# untitled.net
KiCad netlist of a schematic drawn in EAGLE
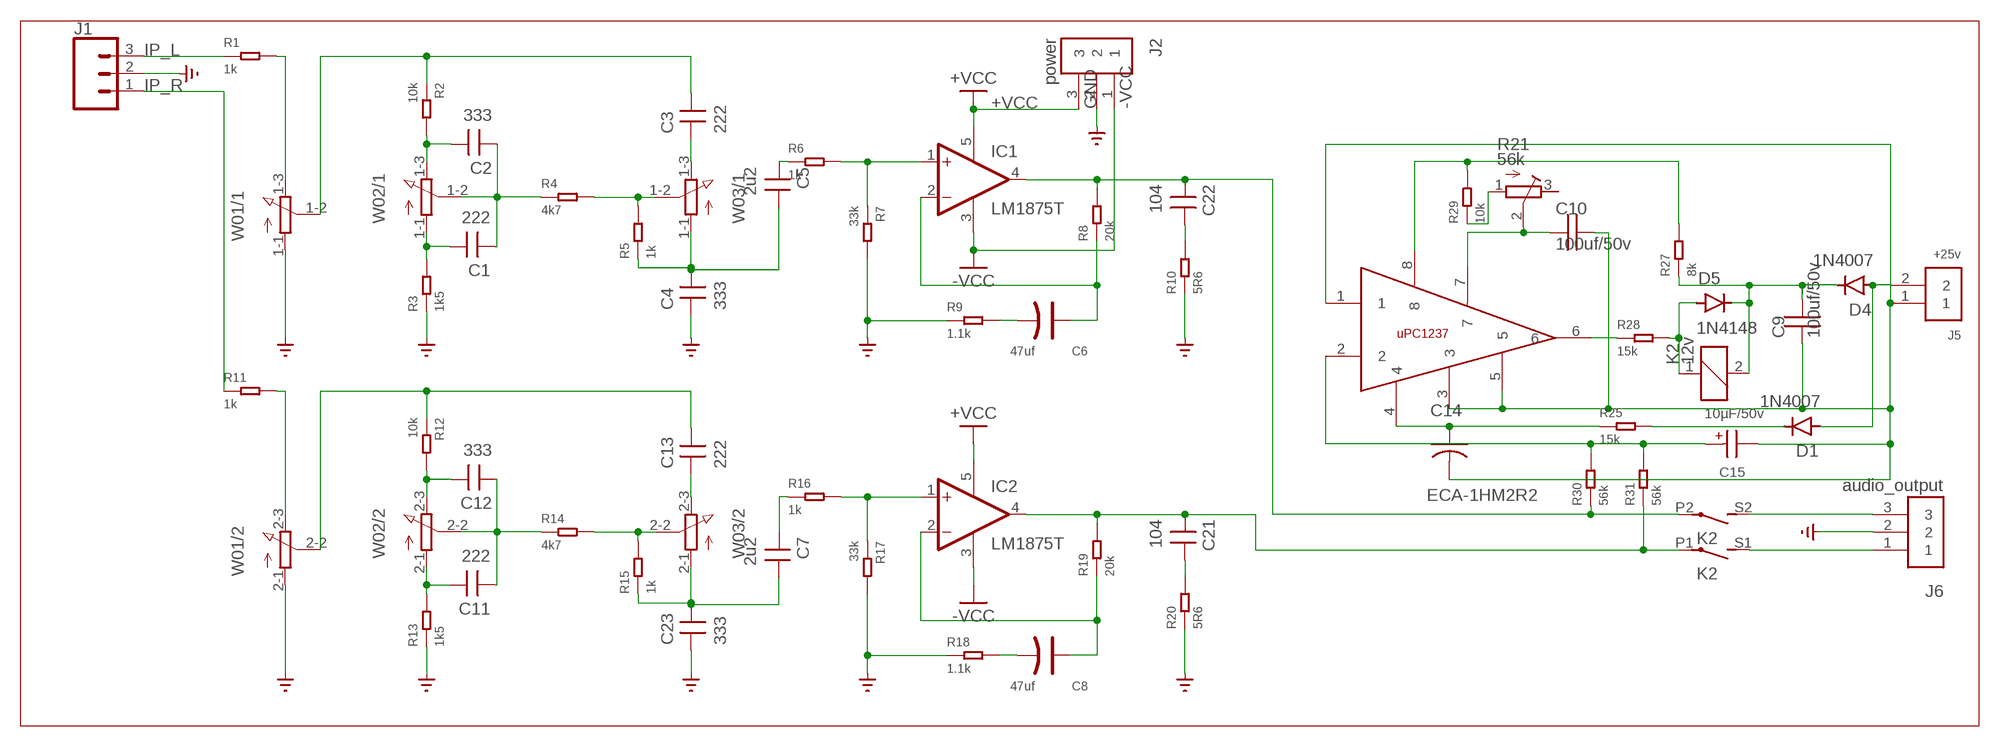
[diagram p0: schematic, sheet 1]

(export (version "E")
  (design (tool "Eeschema 10.0.6"))
  (components
    (comp (ref "C1")
      (value "222")
      (footprint "eagle-import:5.08MM-独石电容")
      (libsource (lib "eagle-import") (part "5.08MM-"))
    )
    (comp (ref "C2")
      (value "333")
      (footprint "eagle-import:5.08MM-独石电容")
      (libsource (lib "eagle-import") (part "5.08MM-"))
    )
    (comp (ref "C3")
      (value "222")
      (footprint "eagle-import:5.08MM-独石电容")
      (libsource (lib "eagle-import") (part "5.08MM-"))
    )
    (comp (ref "C4")
      (value "333")
      (footprint "eagle-import:5.08MM-独石电容")
      (libsource (lib "eagle-import") (part "5.08MM-"))
    )
    (comp (ref "C5")
      (value "2u2")
      (footprint "eagle-import:5.08MM-独石电容")
      (libsource (lib "eagle-import") (part "5.08MM-"))
    )
    (comp (ref "C6")
      (value "47uf")
      (footprint "eagle-import:PC-D5.3MM")
      (fields (field (name "MPN") "KS 100uF/16V"))
      (libsource (lib "eagle-import") (part "DIP-ALUMINUM-47UF-16V(D5-H7MM)"))
    )
    (comp (ref "C7")
      (value "2u2")
      (footprint "eagle-import:5.08MM-独石电容")
      (libsource (lib "eagle-import") (part "5.08MM-"))
    )
    (comp (ref "C8")
      (value "47uf")
      (footprint "eagle-import:PC-D5.3MM")
      (fields (field (name "MPN") "KS 100uF/16V"))
      (libsource (lib "eagle-import") (part "DIP-ALUMINUM-47UF-16V(D5-H7MM)"))
    )
    (comp (ref "C9")
      (value "100uf/50v")
      (footprint "eagle-import:8X12")
      (libsource (lib "eagle-import") (part "50V100UF8X12"))
    )
    (comp (ref "C10")
      (value "100uf/50v")
      (footprint "eagle-import:8X12")
      (libsource (lib "eagle-import") (part "50V100UF8X12"))
    )
    (comp (ref "C11")
      (value "222")
      (footprint "eagle-import:5.08MM-独石电容")
      (libsource (lib "eagle-import") (part "5.08MM-"))
    )
    (comp (ref "C12")
      (value "333")
      (footprint "eagle-import:5.08MM-独石电容")
      (libsource (lib "eagle-import") (part "5.08MM-"))
    )
    (comp (ref "C13")
      (value "222")
      (footprint "eagle-import:5.08MM-独石电容")
      (libsource (lib "eagle-import") (part "5.08MM-"))
    )
    (comp (ref "C14")
      (value "ECA-1HM2R2")
      (footprint "eagle-import:CAP_RADIAL_2MM")
      (fields
        (field (name "DIGIKEY_PART_NUMBER") "P5175-ND")
        (field (name "MANUFACTURER") "Panasonic Electronic Components")
        (field (name "CREATED_BY") "PCBLayout.com")
      )
      (libsource (lib "eagle-import") (part "ECA-1HM2R2"))
    )
    (comp (ref "C15")
      (value "10µF/50v")
      (footprint "eagle-import:WCAP-AT1H_5X11(DXL)")
      (libsource (lib "eagle-import") (part "WCAP-AT1H_5X11_860240272001"))
    )
    (comp (ref "C21")
      (value "104")
      (footprint "eagle-import:5.08MM-独石电容")
      (libsource (lib "eagle-import") (part "5.08MM-"))
    )
    (comp (ref "C22")
      (value "104")
      (footprint "eagle-import:5.08MM-独石电容")
      (libsource (lib "eagle-import") (part "5.08MM-"))
    )
    (comp (ref "C23")
      (value "333")
      (footprint "eagle-import:5.08MM-独石电容")
      (libsource (lib "eagle-import") (part "5.08MM-"))
    )
    (comp (ref "D1")
      (value "1N4007")
      (footprint "eagle-import:DO-41")
      (fields
        (field (name "DIGIKEY_PART_NUMBER") "1N4007MSCT-ND")
        (field (name "MANUFACTURER") "Micro Commercial Co")
        (field (name "CREATED_BY") "PCBLayout.com")
      )
      (libsource (lib "eagle-import") (part "1N4007"))
    )
    (comp (ref "D4")
      (value "1N4007")
      (footprint "eagle-import:DO-41")
      (fields
        (field (name "DIGIKEY_PART_NUMBER") "1N4007MSCT-ND")
        (field (name "MANUFACTURER") "Micro Commercial Co")
        (field (name "CREATED_BY") "PCBLayout.com")
      )
      (libsource (lib "eagle-import") (part "1N4007"))
    )
    (comp (ref "D5")
      (value "1N4148")
      (footprint "eagle-import:DO-41")
      (fields
        (field (name "DIGIKEY_PART_NUMBER") "1N4007MSCT-ND")
        (field (name "MANUFACTURER") "Micro Commercial Co")
        (field (name "MPN") "1N4007")
        (field (name "CREATED_BY") "PCBLayout.com")
      )
      (libsource (lib "eagle-import") (part "1N4007"))
    )
    (comp (ref "IC1")
      (value "LM1875T")
      (footprint "eagle-import:CB367")
      (libsource (lib "eagle-import") (part "LM1875T"))
    )
    (comp (ref "IC2")
      (value "LM1875T")
      (footprint "eagle-import:CB367")
      (libsource (lib "eagle-import") (part "LM1875T"))
    )
    (comp (ref "J1")
      (value "CONN_03POLAR")
      (footprint "eagle-import:MOLEX-1X3")
      (libsource (lib "eagle-import") (part "CONN_03POLAR"))
    )
    (comp (ref "J2")
      (value "power")
      (footprint "eagle-import:TERMINALBLOCK_PLUGGABLE-3-7.62MM")
      (fields
        (field (name "DIGIKEY_PART_NO") "732-2824-ND")
        (field (name "MANUFACTURER") "WURTH ELEKTRONIK")
        (field (name "MPN") "691311400103")
        (field (name "CREATED_BY") "PCBLayout.com")
      )
      (libsource (lib "eagle-import") (part "691311400103"))
    )
    (comp (ref "J5")
      (value "+25v")
      (footprint "eagle-import:61300211121")
      (fields
        (field (name "DIGI_KEY_PART_NUMBER") "732-5315-ND")
        (field (name "MANUFACTURER") "Wurth Electronics Inc.")
        (field (name "MPN") "61300211121")
        (field (name "CREATED_BY") "PCBLayout.com")
      )
      (libsource (lib "eagle-import") (part "61300211121"))
    )
    (comp (ref "J6")
      (value "audio_output")
      (footprint "eagle-import:TERMINALBLOCK_PLUGGABLE-3-7.62MM")
      (fields
        (field (name "DIGIKEY_PART_NO") "732-2824-ND")
        (field (name "MANUFACTURER") "WURTH ELEKTRONIK")
        (field (name "MPN") "691311400103")
        (field (name "CREATED_BY") "PCBLayout.com")
      )
      (libsource (lib "eagle-import") (part "691311400103"))
    )
    (comp (ref "K2")
      (value "12v")
      (footprint "eagle-import:G2R2A")
      (fields (field (name "MPN") "G2R-2A-DC24"))
      (libsource (lib "eagle-import") (part "G2R2A"))
    )
    (comp (ref "R1")
      (value "1k")
      (footprint "eagle-import:PR-D2.3XL6.5MM")
      (fields (field (name "MPN") "FHCFR-1/4W-105J"))
      (libsource (lib "eagle-import") (part "DIP-RES-1M-5%-1/4W(PR-D2.3XL6.5MM)"))
    )
    (comp (ref "R2")
      (value "10k")
      (footprint "eagle-import:PR-D2.3XL6.5MM")
      (fields (field (name "MPN") "FHCFR-1/4W-105J"))
      (libsource (lib "eagle-import") (part "DIP-RES-1M-5%-1/4W(PR-D2.3XL6.5MM)"))
    )
    (comp (ref "R3")
      (value "1k5")
      (footprint "eagle-import:PR-D2.3XL6.5MM")
      (fields (field (name "MPN") "FHCFR-1/4W-105J"))
      (libsource (lib "eagle-import") (part "DIP-RES-1M-5%-1/4W(PR-D2.3XL6.5MM)"))
    )
    (comp (ref "R4")
      (value "4k7")
      (footprint "eagle-import:PR-D2.3XL6.5MM")
      (fields (field (name "MPN") "FHCFR-1/4W-105J"))
      (libsource (lib "eagle-import") (part "DIP-RES-1M-5%-1/4W(PR-D2.3XL6.5MM)"))
    )
    (comp (ref "R5")
      (value "1k")
      (footprint "eagle-import:PR-D2.3XL6.5MM")
      (fields (field (name "MPN") "FHCFR-1/4W-105J"))
      (libsource (lib "eagle-import") (part "DIP-RES-1M-5%-1/4W(PR-D2.3XL6.5MM)"))
    )
    (comp (ref "R6")
      (value "1k")
      (footprint "eagle-import:PR-D2.3XL6.5MM")
      (fields (field (name "MPN") "FHCFR-1/4W-105J"))
      (libsource (lib "eagle-import") (part "DIP-RES-1M-5%-1/4W(PR-D2.3XL6.5MM)"))
    )
    (comp (ref "R7")
      (value "33k")
      (footprint "eagle-import:PR-D2.3XL6.5MM")
      (fields (field (name "MPN") "FHCFR-1/4W-105J"))
      (libsource (lib "eagle-import") (part "DIP-RES-1M-5%-1/4W(PR-D2.3XL6.5MM)"))
    )
    (comp (ref "R8")
      (value "20k")
      (footprint "eagle-import:PR-D2.3XL6.5MM")
      (fields (field (name "MPN") "FHCFR-1/4W-105J"))
      (libsource (lib "eagle-import") (part "DIP-RES-1M-5%-1/4W(PR-D2.3XL6.5MM)"))
    )
    (comp (ref "R9")
      (value "1.1k")
      (footprint "eagle-import:PR-D2.3XL6.5MM")
      (fields (field (name "MPN") "FHCFR-1/4W-105J"))
      (libsource (lib "eagle-import") (part "DIP-RES-1M-5%-1/4W(PR-D2.3XL6.5MM)"))
    )
    (comp (ref "R10")
      (value "5R6")
      (footprint "eagle-import:PR-D2.3XL6.5MM")
      (fields (field (name "MPN") "FHCFR-1/4W-105J"))
      (libsource (lib "eagle-import") (part "DIP-RES-1M-5%-1/4W(PR-D2.3XL6.5MM)"))
    )
    (comp (ref "R11")
      (value "1k")
      (footprint "eagle-import:PR-D2.3XL6.5MM")
      (fields (field (name "MPN") "FHCFR-1/4W-105J"))
      (libsource (lib "eagle-import") (part "DIP-RES-1M-5%-1/4W(PR-D2.3XL6.5MM)"))
    )
    (comp (ref "R12")
      (value "10k")
      (footprint "eagle-import:PR-D2.3XL6.5MM")
      (fields (field (name "MPN") "FHCFR-1/4W-105J"))
      (libsource (lib "eagle-import") (part "DIP-RES-1M-5%-1/4W(PR-D2.3XL6.5MM)"))
    )
    (comp (ref "R13")
      (value "1k5")
      (footprint "eagle-import:PR-D2.3XL6.5MM")
      (fields (field (name "MPN") "FHCFR-1/4W-105J"))
      (libsource (lib "eagle-import") (part "DIP-RES-1M-5%-1/4W(PR-D2.3XL6.5MM)"))
    )
    (comp (ref "R14")
      (value "4k7")
      (footprint "eagle-import:PR-D2.3XL6.5MM")
      (fields (field (name "MPN") "FHCFR-1/4W-105J"))
      (libsource (lib "eagle-import") (part "DIP-RES-1M-5%-1/4W(PR-D2.3XL6.5MM)"))
    )
    (comp (ref "R15")
      (value "1k")
      (footprint "eagle-import:PR-D2.3XL6.5MM")
      (fields (field (name "MPN") "FHCFR-1/4W-105J"))
      (libsource (lib "eagle-import") (part "DIP-RES-1M-5%-1/4W(PR-D2.3XL6.5MM)"))
    )
    (comp (ref "R16")
      (value "1k")
      (footprint "eagle-import:PR-D2.3XL6.5MM")
      (fields (field (name "MPN") "FHCFR-1/4W-105J"))
      (libsource (lib "eagle-import") (part "DIP-RES-1M-5%-1/4W(PR-D2.3XL6.5MM)"))
    )
    (comp (ref "R17")
      (value "33k")
      (footprint "eagle-import:PR-D2.3XL6.5MM")
      (fields (field (name "MPN") "FHCFR-1/4W-105J"))
      (libsource (lib "eagle-import") (part "DIP-RES-1M-5%-1/4W(PR-D2.3XL6.5MM)"))
    )
    (comp (ref "R18")
      (value "1.1k")
      (footprint "eagle-import:PR-D2.3XL6.5MM")
      (fields (field (name "MPN") "FHCFR-1/4W-105J"))
      (libsource (lib "eagle-import") (part "DIP-RES-1M-5%-1/4W(PR-D2.3XL6.5MM)"))
    )
    (comp (ref "R19")
      (value "20k")
      (footprint "eagle-import:PR-D2.3XL6.5MM")
      (fields (field (name "MPN") "FHCFR-1/4W-105J"))
      (libsource (lib "eagle-import") (part "DIP-RES-1M-5%-1/4W(PR-D2.3XL6.5MM)"))
    )
    (comp (ref "R20")
      (value "5R6")
      (footprint "eagle-import:PR-D2.3XL6.5MM")
      (fields (field (name "MPN") "FHCFR-1/4W-105J"))
      (libsource (lib "eagle-import") (part "DIP-RES-1M-5%-1/4W(PR-D2.3XL6.5MM)"))
    )
    (comp (ref "R21")
      (value "56k")
      (footprint "eagle-import:RTRIM3296W")
      (libsource (lib "eagle-import") (part "R-TRIMM3296W"))
    )
    (comp (ref "R25")
      (value "15k")
      (footprint "eagle-import:PR-D2.3XL6.5MM")
      (fields (field (name "MPN") "FHCFR-1/4W-105J"))
      (libsource (lib "eagle-import") (part "DIP-RES-1M-5%-1/4W(PR-D2.3XL6.5MM)"))
    )
    (comp (ref "R27")
      (value "8k")
      (footprint "eagle-import:PR-D2.3XL6.5MM")
      (fields (field (name "MPN") "FHCFR-1/4W-105J"))
      (libsource (lib "eagle-import") (part "DIP-RES-1M-5%-1/4W(PR-D2.3XL6.5MM)"))
    )
    (comp (ref "R28")
      (value "15k")
      (footprint "eagle-import:PR-D2.3XL6.5MM")
      (fields (field (name "MPN") "FHCFR-1/4W-105J"))
      (libsource (lib "eagle-import") (part "DIP-RES-1M-5%-1/4W(PR-D2.3XL6.5MM)"))
    )
    (comp (ref "R29")
      (value "10k")
      (footprint "eagle-import:PR-D2.3XL6.5MM")
      (fields (field (name "MPN") "FHCFR-1/4W-105J"))
      (libsource (lib "eagle-import") (part "DIP-RES-1M-5%-1/4W(PR-D2.3XL6.5MM)"))
    )
    (comp (ref "R30")
      (value "56k")
      (footprint "eagle-import:PR-D2.3XL6.5MM")
      (fields (field (name "MPN") "FHCFR-1/4W-105J"))
      (libsource (lib "eagle-import") (part "DIP-RES-1M-5%-1/4W(PR-D2.3XL6.5MM)"))
    )
    (comp (ref "R31")
      (value "56k")
      (footprint "eagle-import:PR-D2.3XL6.5MM")
      (fields (field (name "MPN") "FHCFR-1/4W-105J"))
      (libsource (lib "eagle-import") (part "DIP-RES-1M-5%-1/4W(PR-D2.3XL6.5MM)"))
    )
    (comp (ref "U2")
      (value "UPC1237HA")
      (footprint "eagle-import:SIP8")
      (libsource (lib "eagle-import") (part "UPC1237HA"))
    )
    (comp (ref "W01")
      (value "3RP/1610G")
      (footprint "eagle-import:3RP_1610G")
      (libsource (lib "eagle-import") (part "3RP/1610G"))
    )
    (comp (ref "W02")
      (value "3RP/1610G")
      (footprint "eagle-import:3RP_1610G")
      (libsource (lib "eagle-import") (part "3RP/1610G"))
    )
    (comp (ref "W03")
      (value "3RP/1610G")
      (footprint "eagle-import:3RP_1610G")
      (libsource (lib "eagle-import") (part "3RP/1610G"))
    )
  )
  (nets
    (net (code "1") (name "+VCC") (class "Default")
      (node (ref "IC1") (pin "5") (pinfunction "V+_5") (pintype "power_in"))
      (node (ref "IC2") (pin "5") (pinfunction "V+_5") (pintype "power_in"))
      (node (ref "J2") (pin "3") (pinfunction "3_3") (pintype "passive"))
    )
    (net (code "2") (name "-VCC") (class "Default")
      (node (ref "IC1") (pin "3") (pinfunction "V-_3") (pintype "power_in"))
      (node (ref "IC2") (pin "3") (pinfunction "V-_3") (pintype "power_in"))
      (node (ref "J2") (pin "1") (pinfunction "1_1") (pintype "passive"))
    )
    (net (code "3") (name "/IP_L") (class "Default")
      (node (ref "J1") (pin "3") (pinfunction "3_3") (pintype "passive"))
      (node (ref "R1") (pin "1") (pinfunction "1_1") (pintype "passive"))
    )
    (net (code "4") (name "/IP_R") (class "Default")
      (node (ref "J1") (pin "1") (pinfunction "1_1") (pintype "passive"))
      (node (ref "R11") (pin "1") (pinfunction "1_1") (pintype "passive"))
    )
    (net (code "5") (name "Net-(C1-1)") (class "Default")
      (node (ref "C1") (pin "P$2") (pinfunction "1_P$2") (pintype "bidirectional"))
      (node (ref "C2") (pin "P$2") (pinfunction "1_P$2") (pintype "bidirectional"))
      (node (ref "R4") (pin "1") (pinfunction "1_1") (pintype "passive"))
      (node (ref "W02") (pin "1-2") (pinfunction "S_1-2") (pintype "passive"))
    )
    (net (code "6") (name "Net-(C1-2)") (class "Default")
      (node (ref "C1") (pin "P$1") (pinfunction "2_P$1") (pintype "bidirectional"))
      (node (ref "R3") (pin "2") (pinfunction "2_2") (pintype "passive"))
      (node (ref "W02") (pin "1-1") (pinfunction "A_1-1") (pintype "passive"))
    )
    (net (code "7") (name "Net-(C2-2)") (class "Default")
      (node (ref "C2") (pin "P$1") (pinfunction "2_P$1") (pintype "bidirectional"))
      (node (ref "R2") (pin "2") (pinfunction "2_2") (pintype "passive"))
      (node (ref "W02") (pin "1-3") (pinfunction "E_1-3") (pintype "passive"))
    )
    (net (code "8") (name "Net-(C3-1)") (class "Default")
      (node (ref "C3") (pin "P$2") (pinfunction "1_P$2") (pintype "bidirectional"))
      (node (ref "W03") (pin "1-3") (pinfunction "E_1-3") (pintype "passive"))
    )
    (net (code "9") (name "Net-(C3-2)") (class "Default")
      (node (ref "C3") (pin "P$1") (pinfunction "2_P$1") (pintype "bidirectional"))
      (node (ref "R2") (pin "1") (pinfunction "1_1") (pintype "passive"))
      (node (ref "W01") (pin "1-2") (pinfunction "S_1-2") (pintype "passive"))
    )
    (net (code "10") (name "Net-(C4-2)") (class "Default")
      (node (ref "C4") (pin "P$1") (pinfunction "2_P$1") (pintype "bidirectional"))
      (node (ref "C5") (pin "P$1") (pinfunction "2_P$1") (pintype "bidirectional"))
      (node (ref "R5") (pin "1") (pinfunction "1_1") (pintype "passive"))
      (node (ref "W03") (pin "1-1") (pinfunction "A_1-1") (pintype "passive"))
    )
    (net (code "11") (name "Net-(C5-1)") (class "Default")
      (node (ref "C5") (pin "P$2") (pinfunction "1_P$2") (pintype "bidirectional"))
      (node (ref "R6") (pin "1") (pinfunction "1_1") (pintype "passive"))
    )
    (net (code "12") (name "Net-(C6-Pad-)") (class "Default")
      (node (ref "C6") (pin "-") (pinfunction "-_-") (pintype "passive"))
      (node (ref "R9") (pin "2") (pinfunction "2_2") (pintype "passive"))
    )
    (net (code "13") (name "Net-(C7-1)") (class "Default")
      (node (ref "C7") (pin "P$2") (pinfunction "1_P$2") (pintype "bidirectional"))
      (node (ref "R16") (pin "1") (pinfunction "1_1") (pintype "passive"))
    )
    (net (code "14") (name "Net-(C8-Pad-)") (class "Default")
      (node (ref "C8") (pin "-") (pinfunction "-_-") (pintype "passive"))
      (node (ref "R18") (pin "2") (pinfunction "2_2") (pintype "passive"))
    )
    (net (code "15") (name "Net-(C9-Pad2)") (class "Default")
      (node (ref "C9") (pin "2") (pinfunction "2_2") (pintype "bidirectional"))
      (node (ref "D4") (pin "C") (pinfunction "C_C") (pintype "passive"))
      (node (ref "D5") (pin "C") (pinfunction "C_C") (pintype "passive"))
      (node (ref "K2") (pin "2") (pinfunction "2_2") (pintype "passive"))
      (node (ref "R27") (pin "1") (pinfunction "1_1") (pintype "passive"))
    )
    (net (code "16") (name "Net-(C11-1)") (class "Default")
      (node (ref "C11") (pin "P$2") (pinfunction "1_P$2") (pintype "bidirectional"))
      (node (ref "C12") (pin "P$2") (pinfunction "1_P$2") (pintype "bidirectional"))
      (node (ref "R14") (pin "1") (pinfunction "1_1") (pintype "passive"))
      (node (ref "W02") (pin "2-2") (pinfunction "S_2-2") (pintype "passive"))
    )
    (net (code "17") (name "Net-(C11-2)") (class "Default")
      (node (ref "C11") (pin "P$1") (pinfunction "2_P$1") (pintype "bidirectional"))
      (node (ref "R13") (pin "2") (pinfunction "2_2") (pintype "passive"))
      (node (ref "W02") (pin "2-1") (pinfunction "A_2-1") (pintype "passive"))
    )
    (net (code "18") (name "Net-(C12-2)") (class "Default")
      (node (ref "C12") (pin "P$1") (pinfunction "2_P$1") (pintype "bidirectional"))
      (node (ref "R12") (pin "2") (pinfunction "2_2") (pintype "passive"))
      (node (ref "W02") (pin "2-3") (pinfunction "E_2-3") (pintype "passive"))
    )
    (net (code "19") (name "Net-(C13-1)") (class "Default")
      (node (ref "C13") (pin "P$2") (pinfunction "1_P$2") (pintype "bidirectional"))
      (node (ref "W03") (pin "2-3") (pinfunction "E_2-3") (pintype "passive"))
    )
    (net (code "20") (name "Net-(C13-2)") (class "Default")
      (node (ref "C13") (pin "P$1") (pinfunction "2_P$1") (pintype "bidirectional"))
      (node (ref "R12") (pin "1") (pinfunction "1_1") (pintype "passive"))
      (node (ref "W01") (pin "2-2") (pinfunction "S_2-2") (pintype "passive"))
    )
    (net (code "21") (name "Net-(C14-Pad1)") (class "Default")
      (node (ref "C14") (pin "1") (pinfunction "1_1") (pintype "passive"))
      (node (ref "R25") (pin "1") (pinfunction "1_1") (pintype "passive"))
      (node (ref "U2") (pin "4") (pinfunction "4_4") (pintype "bidirectional"))
    )
    (net (code "22") (name "Net-(C15-+)") (class "Default")
      (node (ref "C15") (pin "1") (pinfunction "+_1") (pintype "passive"))
      (node (ref "R30") (pin "2") (pinfunction "2_2") (pintype "passive"))
      (node (ref "R31") (pin "2") (pinfunction "2_2") (pintype "passive"))
      (node (ref "U2") (pin "2") (pinfunction "2_2") (pintype "bidirectional"))
    )
    (net (code "23") (name "Net-(C15--)") (class "Default")
      (node (ref "C10") (pin "2") (pinfunction "2_2") (pintype "bidirectional"))
      (node (ref "C14") (pin "2") (pinfunction "2_2") (pintype "passive"))
      (node (ref "C15") (pin "2") (pinfunction "-_2") (pintype "passive"))
      (node (ref "C9") (pin "1") (pinfunction "1_1") (pintype "bidirectional"))
      (node (ref "J5") (pin "1") (pinfunction "1_1") (pintype "passive"))
      (node (ref "U2") (pin "1") (pinfunction "1_1") (pintype "bidirectional"))
      (node (ref "U2") (pin "3") (pinfunction "3_3") (pintype "bidirectional"))
      (node (ref "U2") (pin "5") (pinfunction "5_5") (pintype "bidirectional"))
    )
    (net (code "24") (name "Net-(C21-1)") (class "Default")
      (node (ref "C21") (pin "P$2") (pinfunction "1_P$2") (pintype "bidirectional"))
      (node (ref "IC2") (pin "4") (pinfunction "OUT_4") (pintype "output"))
      (node (ref "K2") (pin "P1") (pinfunction "P_P1") (pintype "passive"))
      (node (ref "R19") (pin "2") (pinfunction "2_2") (pintype "passive"))
      (node (ref "R31") (pin "1") (pinfunction "1_1") (pintype "passive"))
    )
    (net (code "25") (name "Net-(C21-2)") (class "Default")
      (node (ref "C21") (pin "P$1") (pinfunction "2_P$1") (pintype "bidirectional"))
      (node (ref "R20") (pin "2") (pinfunction "2_2") (pintype "passive"))
    )
    (net (code "26") (name "Net-(C22-1)") (class "Default")
      (node (ref "C22") (pin "P$2") (pinfunction "1_P$2") (pintype "bidirectional"))
      (node (ref "IC1") (pin "4") (pinfunction "OUT_4") (pintype "output"))
      (node (ref "K2") (pin "P2") (pinfunction "P_P2") (pintype "passive"))
      (node (ref "R30") (pin "1") (pinfunction "1_1") (pintype "passive"))
      (node (ref "R8") (pin "2") (pinfunction "2_2") (pintype "passive"))
    )
    (net (code "27") (name "Net-(C22-2)") (class "Default")
      (node (ref "C22") (pin "P$1") (pinfunction "2_P$1") (pintype "bidirectional"))
      (node (ref "R10") (pin "2") (pinfunction "2_2") (pintype "passive"))
    )
    (net (code "28") (name "Net-(C23-2)") (class "Default")
      (node (ref "C23") (pin "P$1") (pinfunction "2_P$1") (pintype "bidirectional"))
      (node (ref "C7") (pin "P$1") (pinfunction "2_P$1") (pintype "bidirectional"))
      (node (ref "R15") (pin "1") (pinfunction "1_1") (pintype "passive"))
      (node (ref "W03") (pin "2-1") (pinfunction "A_2-1") (pintype "passive"))
    )
    (net (code "29") (name "Net-(D1-PadA)") (class "Default")
      (node (ref "D1") (pin "A") (pinfunction "A_A") (pintype "passive"))
      (node (ref "D4") (pin "A") (pinfunction "A_A") (pintype "passive"))
      (node (ref "J5") (pin "2") (pinfunction "2_2") (pintype "passive"))
    )
    (net (code "30") (name "Net-(D1-PadC)") (class "Default")
      (node (ref "D1") (pin "C") (pinfunction "C_C") (pintype "passive"))
      (node (ref "R25") (pin "2") (pinfunction "2_2") (pintype "passive"))
    )
    (net (code "31") (name "Net-(D5-PadA)") (class "Default")
      (node (ref "D5") (pin "A") (pinfunction "A_A") (pintype "passive"))
      (node (ref "K2") (pin "1") (pinfunction "1_1") (pintype "passive"))
      (node (ref "R28") (pin "2") (pinfunction "2_2") (pintype "passive"))
    )
    (net (code "32") (name "Net-(IC1-+IN)") (class "Default")
      (node (ref "IC1") (pin "1") (pinfunction "+IN_1") (pintype "input"))
      (node (ref "R6") (pin "2") (pinfunction "2_2") (pintype "passive"))
      (node (ref "R7") (pin "1") (pinfunction "1_1") (pintype "passive"))
    )
    (net (code "33") (name "Net-(IC1--IN)") (class "Default")
      (node (ref "C6") (pin "+") (pinfunction "+_+") (pintype "passive"))
      (node (ref "IC1") (pin "2") (pinfunction "-IN_2") (pintype "input"))
      (node (ref "R8") (pin "1") (pinfunction "1_1") (pintype "passive"))
    )
    (net (code "34") (name "Net-(IC2-+IN)") (class "Default")
      (node (ref "IC2") (pin "1") (pinfunction "+IN_1") (pintype "input"))
      (node (ref "R16") (pin "2") (pinfunction "2_2") (pintype "passive"))
      (node (ref "R17") (pin "1") (pinfunction "1_1") (pintype "passive"))
    )
    (net (code "35") (name "Net-(IC2--IN)") (class "Default")
      (node (ref "C8") (pin "+") (pinfunction "+_+") (pintype "passive"))
      (node (ref "IC2") (pin "2") (pinfunction "-IN_2") (pintype "input"))
      (node (ref "R19") (pin "1") (pinfunction "1_1") (pintype "passive"))
    )
    (net (code "36") (name "Net-(K2B-S)") (class "Default")
      (node (ref "J6") (pin "1") (pinfunction "1_1") (pintype "passive"))
      (node (ref "K2") (pin "S1") (pinfunction "S_S1") (pintype "passive"))
    )
    (net (code "37") (name "Net-(K2C-S)") (class "Default")
      (node (ref "J6") (pin "3") (pinfunction "3_3") (pintype "passive"))
      (node (ref "K2") (pin "S2") (pinfunction "S_S2") (pintype "passive"))
    )
    (net (code "38") (name "Net-(R21-A)") (class "Default")
      (node (ref "R21") (pin "1") (pinfunction "A_1") (pintype "passive"))
      (node (ref "R29") (pin "1") (pinfunction "1_1") (pintype "passive"))
    )
    (net (code "39") (name "Net-(R21-S)") (class "Default")
      (node (ref "C10") (pin "1") (pinfunction "1_1") (pintype "bidirectional"))
      (node (ref "R21") (pin "2") (pinfunction "S_2") (pintype "passive"))
      (node (ref "U2") (pin "7") (pinfunction "7_7") (pintype "bidirectional"))
    )
    (net (code "40") (name "Net-(R27-Pad2)") (class "Default")
      (node (ref "R27") (pin "2") (pinfunction "2_2") (pintype "passive"))
      (node (ref "R29") (pin "2") (pinfunction "2_2") (pintype "passive"))
      (node (ref "U2") (pin "8") (pinfunction "8_8") (pintype "bidirectional"))
    )
    (net (code "41") (name "Net-(R28-Pad1)") (class "Default")
      (node (ref "R28") (pin "1") (pinfunction "1_1") (pintype "passive"))
      (node (ref "U2") (pin "6") (pinfunction "6_6") (pintype "bidirectional"))
    )
    (net (code "42") (name "Net-(W01A-E)") (class "Default")
      (node (ref "R1") (pin "2") (pinfunction "2_2") (pintype "passive"))
      (node (ref "W01") (pin "1-3") (pinfunction "E_1-3") (pintype "passive"))
    )
    (net (code "43") (name "Net-(W01B-E)") (class "Default")
      (node (ref "R11") (pin "2") (pinfunction "2_2") (pintype "passive"))
      (node (ref "W01") (pin "2-3") (pinfunction "E_2-3") (pintype "passive"))
    )
    (net (code "44") (name "Net-(W03A-S)") (class "Default")
      (node (ref "R4") (pin "2") (pinfunction "2_2") (pintype "passive"))
      (node (ref "R5") (pin "2") (pinfunction "2_2") (pintype "passive"))
      (node (ref "W03") (pin "1-2") (pinfunction "S_1-2") (pintype "passive"))
    )
    (net (code "45") (name "Net-(W03B-S)") (class "Default")
      (node (ref "R14") (pin "2") (pinfunction "2_2") (pintype "passive"))
      (node (ref "R15") (pin "2") (pinfunction "2_2") (pintype "passive"))
      (node (ref "W03") (pin "2-2") (pinfunction "S_2-2") (pintype "passive"))
    )
    (net (code "46") (name "SUPPLY0_GND_") (class "Default")
      (node (ref "C23") (pin "P$2") (pinfunction "1_P$2") (pintype "bidirectional"))
      (node (ref "C4") (pin "P$2") (pinfunction "1_P$2") (pintype "bidirectional"))
      (node (ref "J1") (pin "2") (pinfunction "2_2") (pintype "passive"))
      (node (ref "J2") (pin "2") (pinfunction "2_2") (pintype "passive"))
      (node (ref "J6") (pin "2") (pinfunction "2_2") (pintype "passive"))
      (node (ref "R10") (pin "1") (pinfunction "1_1") (pintype "passive"))
      (node (ref "R13") (pin "1") (pinfunction "1_1") (pintype "passive"))
      (node (ref "R17") (pin "2") (pinfunction "2_2") (pintype "passive"))
      (node (ref "R18") (pin "1") (pinfunction "1_1") (pintype "passive"))
      (node (ref "R20") (pin "1") (pinfunction "1_1") (pintype "passive"))
      (node (ref "R3") (pin "1") (pinfunction "1_1") (pintype "passive"))
      (node (ref "R7") (pin "2") (pinfunction "2_2") (pintype "passive"))
      (node (ref "R9") (pin "1") (pinfunction "1_1") (pintype "passive"))
      (node (ref "W01") (pin "1-1") (pinfunction "A_1-1") (pintype "passive"))
      (node (ref "W01") (pin "2-1") (pinfunction "A_2-1") (pintype "passive"))
    )
    (net (code "47") (name "unconnected-(R21-E-Pad3)") (class "Default")
      (node (ref "R21") (pin "3") (pinfunction "E_3") (pintype "passive"))
    )
  )
)
